# BACKPMAN30_PwrSw.net
KiCad netlist of a schematic drawn in Altium Designer
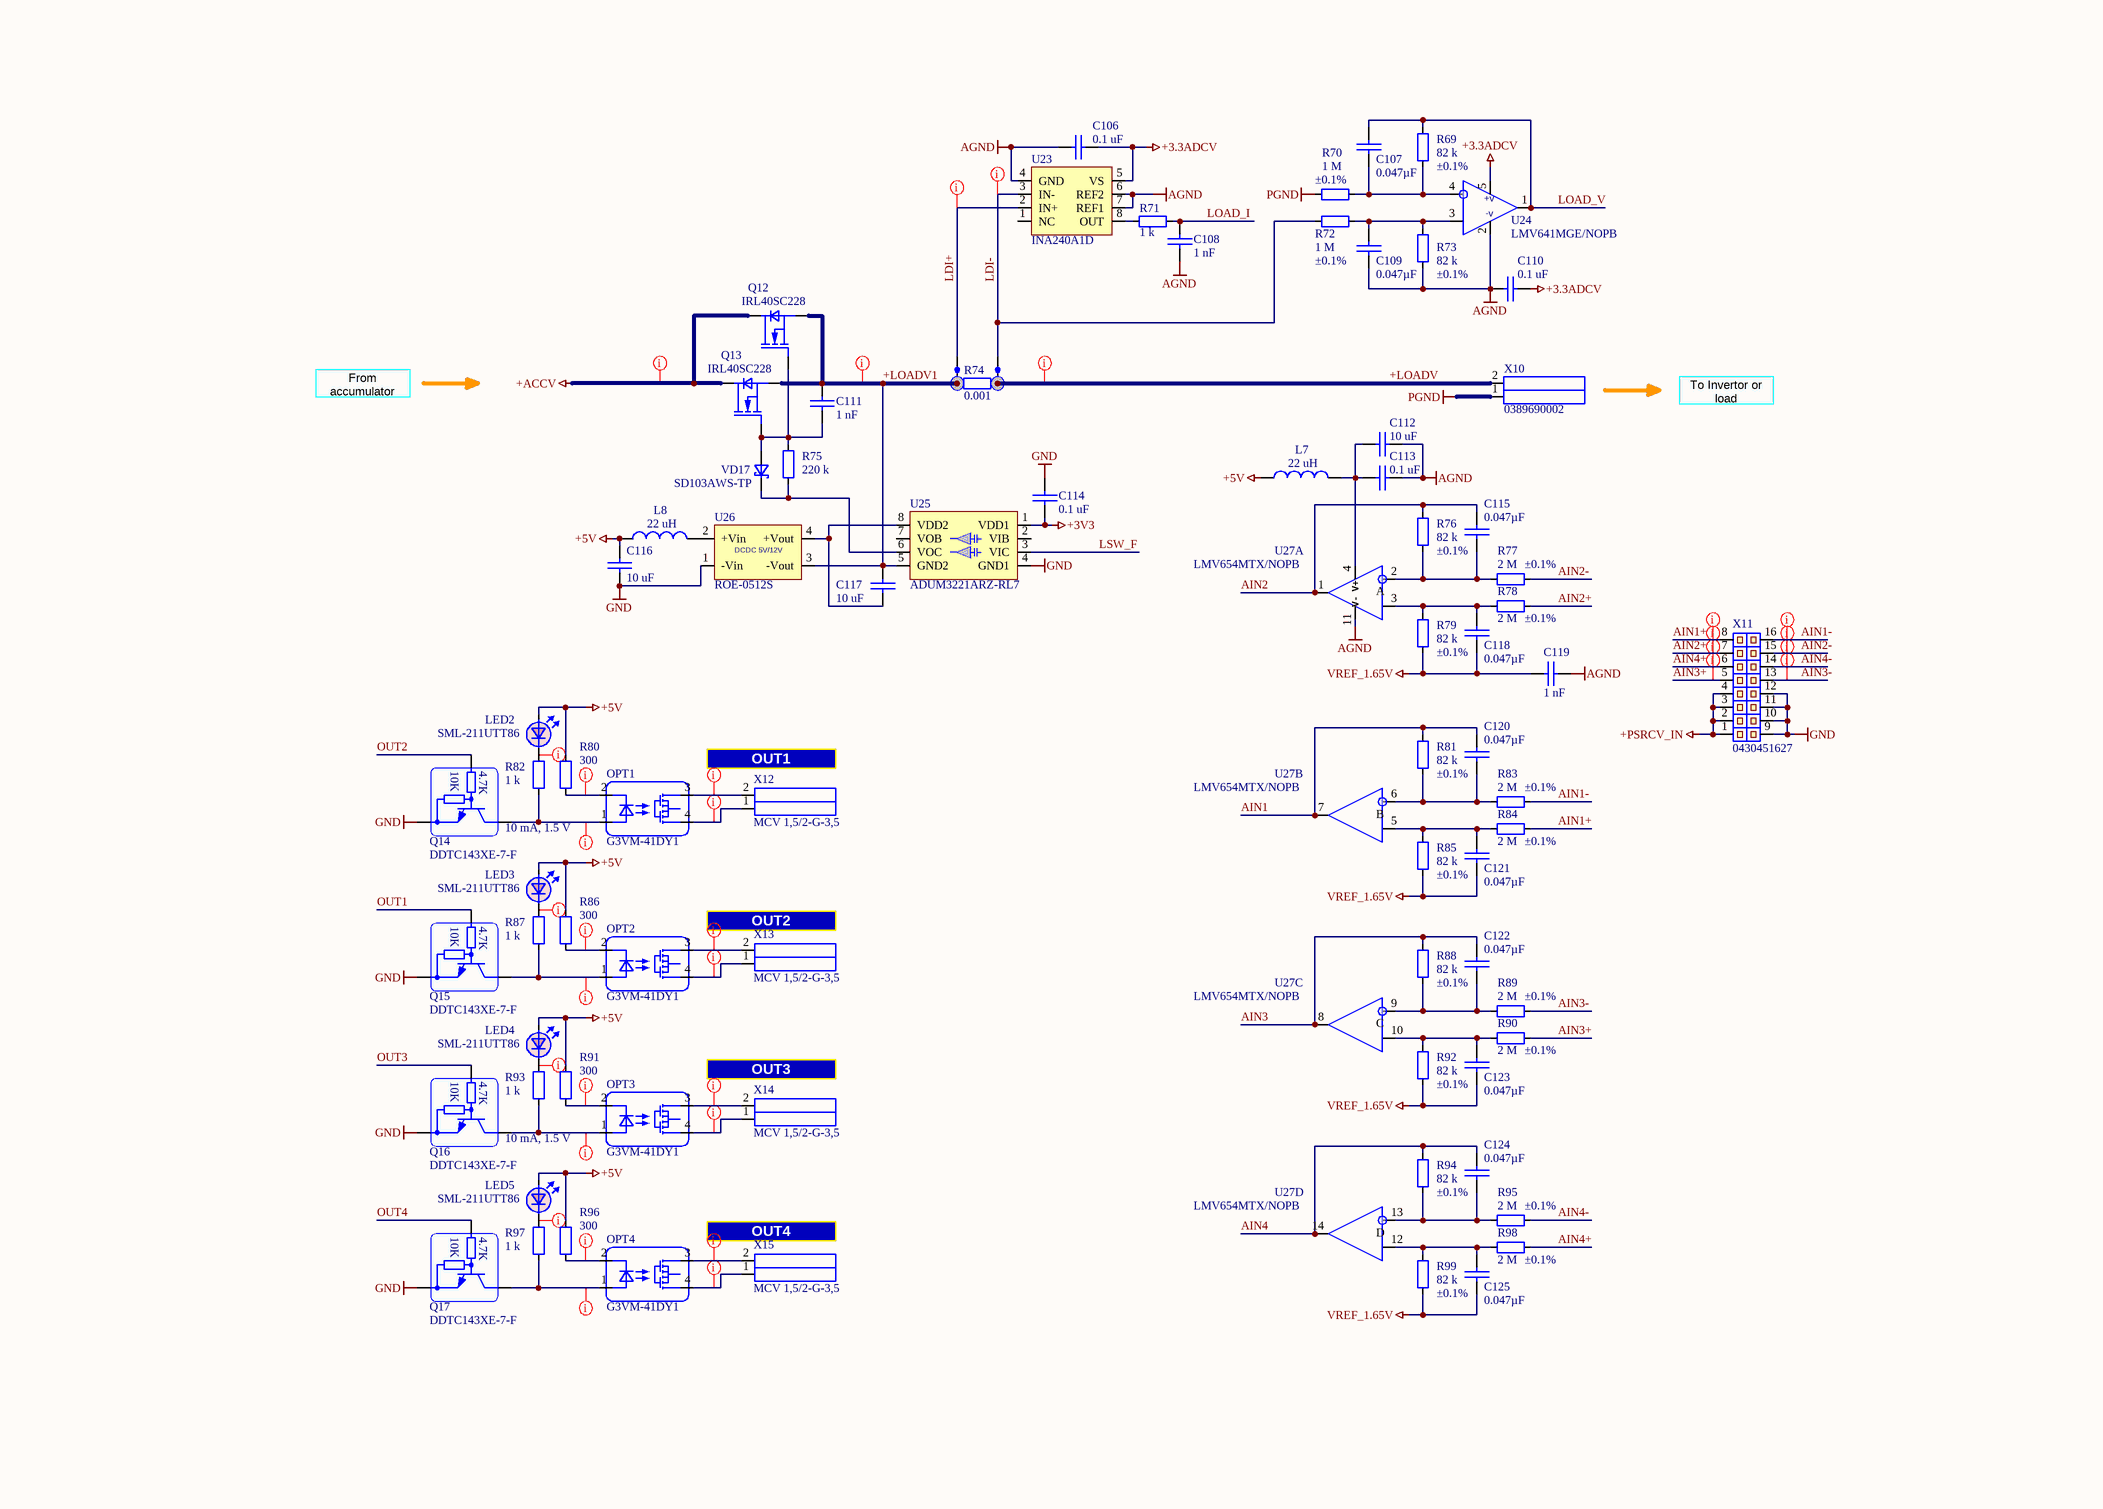
[diagram p0: BACKPMAN30_PwrSw.SchDoc]

(export (version "E")
  (design (tool "Eeschema 10.0.6"))
  (components
    (comp (ref "B4")
      (value "Net tie 0.3mm")
      (footprint "Net tee 0.3 mm")
      (libsource (lib "ea_Mechanical") (part "Net tie 0.3mm"))
    )
    (comp (ref "B5")
      (value "Net tie 0.3mm")
      (footprint "Net tee 0.3 mm")
      (libsource (lib "ea_Mechanical") (part "Net tie 0.3mm"))
    )
    (comp (ref "C106")
      (value "0.1 uF")
      (footprint "1608[0603]")
      (description "0.1 µF ±10% 50V Ceramic Capacitor X7R 0603 (1608 Metric), -55°C ~ 125°C")
      (fields
        (field (name "MANUFACTURER") "Walsin Technology Corporation")
        (field (name "PARTNUM") "1292-1643-1-ND")
      )
      (libsource (lib "ea_Capacitors_0603") (part "0603B104K500CT"))
    )
    (comp (ref "C107")
      (value "0.047µF")
      (footprint "0603 CAP")
      (description "0.047µF, ±5%, 50V, X7R, 0603 (1608 Metric), -55°C ~ 125°C, -, General Purpose")
      (fields (field (name "PART NUMBER") "CC0603JRX7R9BB473") (field (name "MANUFACTURER") "Yageo"))
      (libsource (lib "ea_PassivComps") (part "Capacitor"))
    )
    (comp (ref "C108")
      (value "1 nF")
      (footprint "0603 CAP")
      (description "1000pF, ±5%, 50V, X7R, 0603 (1608 Metric), -55°C ~ 125°C, -, General Purpose")
      (fields (field (name "PART NUMBER") "CC0603JRX7R9BB102") (field (name "MANUFACTURER") "Yageo"))
      (libsource (lib "ea_PassivComps") (part "Capacitor"))
    )
    (comp (ref "C109")
      (value "0.047µF")
      (footprint "0603 CAP")
      (description "0.047µF, ±5%, 50V, X7R, 0603 (1608 Metric), -55°C ~ 125°C, -, General Purpose")
      (fields (field (name "PART NUMBER") "CC0603JRX7R9BB473") (field (name "MANUFACTURER") "Yageo"))
      (libsource (lib "ea_PassivComps") (part "Capacitor"))
    )
    (comp (ref "C110")
      (value "0.1 uF")
      (footprint "1608[0603]")
      (description "0.1 µF ±10% 50V Ceramic Capacitor X7R 0603 (1608 Metric), -55°C ~ 125°C")
      (fields
        (field (name "MANUFACTURER") "Walsin Technology Corporation")
        (field (name "PARTNUM") "1292-1643-1-ND")
      )
      (libsource (lib "ea_Capacitors_0603") (part "0603B104K500CT"))
    )
    (comp (ref "C111")
      (value "1 nF")
      (footprint "0603 CAP")
      (description "1000pF, ±5%, 50V, X7R, 0603 (1608 Metric), -55°C ~ 125°C, -, General Purpose")
      (fields (field (name "PART NUMBER") "CC0603JRX7R9BB102") (field (name "MANUFACTURER") "Yageo"))
      (libsource (lib "ea_PassivComps") (part "Capacitor"))
    )
    (comp (ref "C112")
      (value "10 uF")
      (footprint "3225[1210]")
      (description "10 µF ±10%, 50V, Ceramic Capacitor X7R, 1210 (3225 Metric), -55°C ~ 125°C")
      (fields
        (field (name "MANUFACTURER") "CAL-CHIP ELECTRONICS, INC.")
        (field (name "PARTNUM") "2571-GMC32X7R106K50NTTR-ND")
      )
      (libsource (lib "ea_Capacitors_1210") (part "GMC32X7R106K50NT"))
    )
    (comp (ref "C113")
      (value "0.1 uF")
      (footprint "1608[0603]")
      (description "0.1 µF ±10% 50V Ceramic Capacitor X7R 0603 (1608 Metric), -55°C ~ 125°C")
      (fields
        (field (name "MANUFACTURER") "Walsin Technology Corporation")
        (field (name "PARTNUM") "1292-1643-1-ND")
      )
      (libsource (lib "ea_Capacitors_0603") (part "0603B104K500CT"))
    )
    (comp (ref "C114")
      (value "0.1 uF")
      (footprint "1608[0603]")
      (description "0.1 µF ±10% 50V Ceramic Capacitor X7R 0603 (1608 Metric), -55°C ~ 125°C")
      (fields
        (field (name "TOLERANCE") "+-10%")
        (field (name "MANUFACTURER") "Walsin Technology Corporation")
      )
      (libsource (lib "ea_Capacitors_0603") (part "0603B104K500CT"))
    )
    (comp (ref "C115")
      (value "0.047µF")
      (footprint "0603 CAP")
      (description "0.047µF, ±5%, 50V, X7R, 0603 (1608 Metric), -55°C ~ 125°C, -, General Purpose")
      (fields (field (name "PART NUMBER") "CC0603JRX7R9BB473") (field (name "MANUFACTURER") "Yageo"))
      (libsource (lib "ea_PassivComps") (part "Capacitor"))
    )
    (comp (ref "C116")
      (value "10 uF")
      (footprint "3225[1210]")
      (description "10 µF ±10%, 50V, Ceramic Capacitor X7R, 1210 (3225 Metric), -55°C ~ 125°C")
      (fields
        (field (name "MANUFACTURER") "CAL-CHIP ELECTRONICS, INC.")
        (field (name "PARTNUM") "2571-GMC32X7R106K50NTTR-ND")
      )
      (libsource (lib "ea_Capacitors_1210") (part "GMC32X7R106K50NT"))
    )
    (comp (ref "C117")
      (value "10 uF")
      (footprint "3225[1210]")
      (description "10 µF ±10%, 50V, Ceramic Capacitor X7R, 1210 (3225 Metric), -55°C ~ 125°C")
      (fields
        (field (name "MANUFACTURER") "CAL-CHIP ELECTRONICS, INC.")
        (field (name "PARTNUM") "2571-GMC32X7R106K50NTTR-ND")
      )
      (libsource (lib "ea_Capacitors_1210") (part "GMC32X7R106K50NT"))
    )
    (comp (ref "C118")
      (value "0.047µF")
      (footprint "0603 CAP")
      (description "0.047µF, ±5%, 50V, X7R, 0603 (1608 Metric), -55°C ~ 125°C, -, General Purpose")
      (fields (field (name "PART NUMBER") "CC0603JRX7R9BB473") (field (name "MANUFACTURER") "Yageo"))
      (libsource (lib "ea_PassivComps") (part "Capacitor"))
    )
    (comp (ref "C119")
      (value "1 nF")
      (footprint "0603 CAP")
      (description "1000pF, ±5%, 50V, X7R, 0603 (1608 Metric), -55°C ~ 125°C, -, General Purpose")
      (fields (field (name "PART NUMBER") "CC0603JRX7R9BB102") (field (name "MANUFACTURER") "Yageo"))
      (libsource (lib "ea_PassivComps") (part "Capacitor"))
    )
    (comp (ref "C120")
      (value "0.047µF")
      (footprint "0603 CAP")
      (description "0.047µF, ±5%, 50V, X7R, 0603 (1608 Metric), -55°C ~ 125°C, -, General Purpose")
      (fields (field (name "PART NUMBER") "CC0603JRX7R9BB473") (field (name "MANUFACTURER") "Yageo"))
      (libsource (lib "ea_PassivComps") (part "Capacitor"))
    )
    (comp (ref "C121")
      (value "0.047µF")
      (footprint "0603 CAP")
      (description "0.047µF, ±5%, 50V, X7R, 0603 (1608 Metric), -55°C ~ 125°C, -, General Purpose")
      (fields (field (name "PART NUMBER") "CC0603JRX7R9BB473") (field (name "MANUFACTURER") "Yageo"))
      (libsource (lib "ea_PassivComps") (part "Capacitor"))
    )
    (comp (ref "C122")
      (value "0.047µF")
      (footprint "0603 CAP")
      (description "0.047µF, ±5%, 50V, X7R, 0603 (1608 Metric), -55°C ~ 125°C, -, General Purpose")
      (fields (field (name "PART NUMBER") "CC0603JRX7R9BB473") (field (name "MANUFACTURER") "Yageo"))
      (libsource (lib "ea_PassivComps") (part "Capacitor"))
    )
    (comp (ref "C123")
      (value "0.047µF")
      (footprint "0603 CAP")
      (description "0.047µF, ±5%, 50V, X7R, 0603 (1608 Metric), -55°C ~ 125°C, -, General Purpose")
      (fields (field (name "PART NUMBER") "CC0603JRX7R9BB473") (field (name "MANUFACTURER") "Yageo"))
      (libsource (lib "ea_PassivComps") (part "Capacitor"))
    )
    (comp (ref "C124")
      (value "0.047µF")
      (footprint "0603 CAP")
      (description "0.047µF, ±5%, 50V, X7R, 0603 (1608 Metric), -55°C ~ 125°C, -, General Purpose")
      (fields (field (name "PART NUMBER") "CC0603JRX7R9BB473") (field (name "MANUFACTURER") "Yageo"))
      (libsource (lib "ea_PassivComps") (part "Capacitor"))
    )
    (comp (ref "C125")
      (value "0.047µF")
      (footprint "0603 CAP")
      (description "0.047µF, ±5%, 50V, X7R, 0603 (1608 Metric), -55°C ~ 125°C, -, General Purpose")
      (fields (field (name "PART NUMBER") "CC0603JRX7R9BB473") (field (name "MANUFACTURER") "Yageo"))
      (libsource (lib "ea_PassivComps") (part "Capacitor"))
    )
    (comp (ref "L7")
      (value "22 uH")
      (footprint "2518")
      (description "22 µH Unshielded Wirewound Inductor, 490 mA, 560mOhm, 1007 (2518 Metric)")
      (fields (field (name "MANUFACTURER") "Taiyo Yuden") (field (name "PARTNUM") "587-2439-1-ND"))
      (libsource (lib "ea_Inductors") (part "BRC2518T220K"))
    )
    (comp (ref "L8")
      (value "22 uH")
      (footprint "2518")
      (description "22 µH Unshielded Wirewound Inductor, 490 mA, 560mOhm, 1007 (2518 Metric)")
      (fields (field (name "MANUFACTURER") "Taiyo Yuden") (field (name "PARTNUM") "587-2439-1-ND"))
      (libsource (lib "ea_Inductors") (part "BRC2518T220K"))
    )
    (comp (ref "LED2")
      (value "SML-211UTT86")
      (footprint "0805 LED")
      (description "0805 red LED, hibright, 2 mA, 1.8V, 130°")
      (fields (field (name "MANUFACTURER") "Rohm") (field (name "PARTNUM") "511-1292-1-ND"))
      (libsource (lib "ea_Indicators") (part "SML-211UTT86"))
    )
    (comp (ref "LED3")
      (value "SML-211UTT86")
      (footprint "0805 LED")
      (description "0805 red LED, hibright, 2 mA, 1.8V, 130°")
      (fields (field (name "MANUFACTURER") "Rohm") (field (name "PARTNUM") "511-1292-1-ND"))
      (libsource (lib "ea_Indicators") (part "SML-211UTT86"))
    )
    (comp (ref "LED4")
      (value "SML-211UTT86")
      (footprint "0805 LED")
      (description "0805 red LED, hibright, 2 mA, 1.8V, 130°")
      (fields (field (name "MANUFACTURER") "Rohm") (field (name "PARTNUM") "511-1292-1-ND"))
      (libsource (lib "ea_Indicators") (part "SML-211UTT86"))
    )
    (comp (ref "LED5")
      (value "SML-211UTT86")
      (footprint "0805 LED")
      (description "0805 red LED, hibright, 2 mA, 1.8V, 130°")
      (fields (field (name "MANUFACTURER") "Rohm") (field (name "PARTNUM") "511-1292-1-ND"))
      (libsource (lib "ea_Indicators") (part "SML-211UTT86"))
    )
    (comp (ref "OPT1")
      (value "G3VM-41DY1")
      (footprint "4-SMD Omron")
      (description "Solid State AC DC SPST-NO (1 Form A), 0-40V, 2A, 4-SMD (0.300\", 7.62mm)")
      (fields
        (field (name "MANUFACTURER") "Omron Electronics Inc-EMC Div")
        (field (name "PARTNUM") "Z5418CT-ND")
      )
      (libsource (lib "ea_Opto") (part "G3VM-41DY1"))
    )
    (comp (ref "OPT2")
      (value "G3VM-41DY1")
      (footprint "4-SMD Omron")
      (description "Solid State AC DC SPST-NO (1 Form A), 0-40V, 2A, 4-SMD (0.300\", 7.62mm)")
      (fields
        (field (name "MANUFACTURER") "Omron Electronics Inc-EMC Div")
        (field (name "PARTNUM") "Z5418CT-ND")
      )
      (libsource (lib "ea_Opto") (part "G3VM-41DY1"))
    )
    (comp (ref "OPT3")
      (value "G3VM-41DY1")
      (footprint "4-SMD Omron")
      (description "Solid State AC DC SPST-NO (1 Form A), 0-40V, 2A, 4-SMD (0.300\", 7.62mm)")
      (fields
        (field (name "MANUFACTURER") "Omron Electronics Inc-EMC Div")
        (field (name "PARTNUM") "Z5418CT-ND")
      )
      (libsource (lib "ea_Opto") (part "G3VM-41DY1"))
    )
    (comp (ref "OPT4")
      (value "G3VM-41DY1")
      (footprint "4-SMD Omron")
      (description "Solid State AC DC SPST-NO (1 Form A), 0-40V, 2A, 4-SMD (0.300\", 7.62mm)")
      (fields
        (field (name "MANUFACTURER") "Omron Electronics Inc-EMC Div")
        (field (name "PARTNUM") "Z5418CT-ND")
      )
      (libsource (lib "ea_Opto") (part "G3VM-41DY1"))
    )
    (comp (ref "Q12")
      (value "IRL40SC228")
      (footprint "D2Pak-7pin")
      (description "N-Channel 40 V 557A (Tc) 416W (Tc), 0.65mOhm @ 100A, 10V,  Surface Mount D2PAK (7-Lead)")
      (fields
        (field (name "MANUFACTURER") "Infineon Technologies")
        (field (name "PARTNUM") "IRL40SC228CT-ND")
      )
      (libsource (lib "ea_MOSFET_&_drivers") (part "IRL40SC228"))
    )
    (comp (ref "Q13")
      (value "IRL40SC228")
      (footprint "D2Pak-7pin")
      (description "N-Channel 40 V 557A (Tc) 416W (Tc), 0.65mOhm @ 100A, 10V,  Surface Mount D2PAK (7-Lead)")
      (fields
        (field (name "MANUFACTURER") "Infineon Technologies")
        (field (name "PARTNUM") "IRL40SC228CT-ND")
      )
      (libsource (lib "ea_MOSFET_&_drivers") (part "IRL40SC228"))
    )
    (comp (ref "Q14")
      (value "DDTC143XE-7-F")
      (footprint "SOT-523F")
      (fields
        (field (name "MANUFACTURER") "Diodes Incorporated")
        (field (name "PARTNUM") "DDTC143XE-FDICT-ND")
      )
      (libsource (lib "ea_Transistors") (part "DDTC143XE-7-F"))
    )
    (comp (ref "Q15")
      (value "DDTC143XE-7-F")
      (footprint "SOT-523F")
      (fields
        (field (name "MANUFACTURER") "Diodes Incorporated")
        (field (name "PARTNUM") "DDTC143XE-FDICT-ND")
      )
      (libsource (lib "ea_Transistors") (part "DDTC143XE-7-F"))
    )
    (comp (ref "Q16")
      (value "DDTC143XE-7-F")
      (footprint "SOT-523F")
      (fields
        (field (name "MANUFACTURER") "Diodes Incorporated")
        (field (name "PARTNUM") "DDTC143XE-FDICT-ND")
      )
      (libsource (lib "ea_Transistors") (part "DDTC143XE-7-F"))
    )
    (comp (ref "Q17")
      (value "DDTC143XE-7-F")
      (footprint "SOT-523F")
      (fields
        (field (name "MANUFACTURER") "Diodes Incorporated")
        (field (name "PARTNUM") "DDTC143XE-FDICT-ND")
      )
      (libsource (lib "ea_Transistors") (part "DDTC143XE-7-F"))
    )
    (comp (ref "R69")
      (value "82 k")
      (footprint "0603")
      (fields
        (field (name "MANUFACTURER") "Panasonic Electronic Components")
        (field (name "TOLERANCE") "±0.1%")
        (field (name "VOLTAGE") "75V")
        (field (name "PARTNUM") "P82KDBCT-ND")
      )
      (libsource (lib "") (part "Resistor_1"))
    )
    (comp (ref "R70")
      (value "1 M")
      (footprint "0805")
      (description "1M, ±0.1%, ±50ppm/°C, 0.125W, 1/8W Chip Resistor 0805 (2012 Metric) - Thin Film,-55°C ~ 155°C")
      (fields
        (field (name "MANUFACTURER") "YAGEO")
        (field (name "TOLERANCE") "±0.1%")
        (field (name "PARTNUM") "YAG4967CT-ND")
      )
      (libsource (lib "ea_Resistors_0805") (part "RT0805BRE071ML"))
    )
    (comp (ref "R71")
      (value "1 k")
      (footprint "0603")
      (fields
        (field (name "MANUFACTURER") "Stackpole Electronics Inc.")
        (field (name "TOLERANCE") "±1%")
        (field (name "VOLTAGE") "75V")
      )
      (libsource (lib "ea_PassivComps") (part "Resistor"))
    )
    (comp (ref "R72")
      (value "1 M")
      (footprint "0805")
      (description "1M, ±0.1%, ±50ppm/°C, 0.125W, 1/8W Chip Resistor 0805 (2012 Metric) - Thin Film,-55°C ~ 155°C")
      (fields
        (field (name "MANUFACTURER") "YAGEO")
        (field (name "TOLERANCE") "±0.1%")
        (field (name "PARTNUM") "YAG4967CT-ND")
      )
      (libsource (lib "ea_Resistors_0805") (part "RT0805BRE071ML"))
    )
    (comp (ref "R73")
      (value "82 k")
      (footprint "0603")
      (fields
        (field (name "MANUFACTURER") "Panasonic Electronic Components")
        (field (name "TOLERANCE") "±0.1%")
        (field (name "VOLTAGE") "75V")
        (field (name "PARTNUM") "P82KDBCT-ND")
      )
      (libsource (lib "") (part "Resistor_1"))
    )
    (comp (ref "R74")
      (value "0.001")
      (footprint "WSR52L000FEA")
      (description "Curr.sens.res. 0.001 OHM 5W 1% 4527 SMD")
      (fields (field (name "MANUFACTURER") "Vishay/Dale") (field (name "TOLERANCE") "1%"))
      (libsource (lib "ea_Resistors") (part "WSR51L000FEA"))
    )
    (comp (ref "R75")
      (value "220 k")
      (footprint "0603")
      (fields
        (field (name "MANUFACTURER") "Stackpole Electronics Inc.")
        (field (name "TOLERANCE") "±1%")
        (field (name "VOLTAGE") "75V")
      )
      (libsource (lib "") (part "Resistor_1"))
    )
    (comp (ref "R76")
      (value "82 k")
      (footprint "0603")
      (fields
        (field (name "MANUFACTURER") "Panasonic Electronic Components")
        (field (name "TOLERANCE") "±0.1%")
        (field (name "VOLTAGE") "75V")
        (field (name "PARTNUM") "P82KDBCT-ND")
      )
      (libsource (lib "ea_PassivComps") (part "Resistor"))
    )
    (comp (ref "R77")
      (value "2 M")
      (footprint "0805")
      (description "2M, ±0.1%, ±25ppm/°C, 0.125W, 1/8W Chip Resistor 0805 (2012 Metric) - Thin Film,-55°C ~ 155°C")
      (fields
        (field (name "MANUFACTURER") "TE Connectivity Passive Product")
        (field (name "TOLERANCE") "±0.1%")
        (field (name "PARTNUM") "A119974CT-ND")
      )
      (libsource (lib "ea_Resistors_0805") (part "CPF0805B2M0E"))
    )
    (comp (ref "R78")
      (value "2 M")
      (footprint "0805")
      (description "2M, ±0.1%, ±25ppm/°C, 0.125W, 1/8W Chip Resistor 0805 (2012 Metric) - Thin Film,-55°C ~ 155°C")
      (fields
        (field (name "MANUFACTURER") "TE Connectivity Passive Product")
        (field (name "TOLERANCE") "±0.1%")
        (field (name "PARTNUM") "A119974CT-ND")
      )
      (libsource (lib "ea_Resistors_0805") (part "CPF0805B2M0E"))
    )
    (comp (ref "R79")
      (value "82 k")
      (footprint "0603")
      (fields
        (field (name "MANUFACTURER") "Panasonic Electronic Components")
        (field (name "TOLERANCE") "±0.1%")
        (field (name "VOLTAGE") "75V")
        (field (name "PARTNUM") "P82KDBCT-ND")
      )
      (libsource (lib "ea_PassivComps") (part "Resistor"))
    )
    (comp (ref "R80")
      (value "300")
      (footprint "0603")
      (fields
        (field (name "MANUFACTURER") "Stackpole Electronics Inc.")
        (field (name "TOLERANCE") "±1%")
        (field (name "VOLTAGE") "75V")
      )
      (libsource (lib "") (part "Resistor_1"))
    )
    (comp (ref "R81")
      (value "82 k")
      (footprint "0603")
      (fields
        (field (name "MANUFACTURER") "Panasonic Electronic Components")
        (field (name "TOLERANCE") "±0.1%")
        (field (name "VOLTAGE") "75V")
        (field (name "PARTNUM") "P82KDBCT-ND")
      )
      (libsource (lib "ea_PassivComps") (part "Resistor"))
    )
    (comp (ref "R82")
      (value "1 k")
      (footprint "0603")
      (fields
        (field (name "MANUFACTURER") "Stackpole Electronics Inc.")
        (field (name "TOLERANCE") "±1%")
        (field (name "VOLTAGE") "75V")
      )
      (libsource (lib "") (part "Resistor_1"))
    )
    (comp (ref "R83")
      (value "2 M")
      (footprint "0805")
      (description "2M, ±0.1%, ±25ppm/°C, 0.125W, 1/8W Chip Resistor 0805 (2012 Metric) - Thin Film,-55°C ~ 155°C")
      (fields
        (field (name "MANUFACTURER") "TE Connectivity Passive Product")
        (field (name "TOLERANCE") "±0.1%")
        (field (name "PARTNUM") "A119974CT-ND")
      )
      (libsource (lib "ea_Resistors_0805") (part "CPF0805B2M0E"))
    )
    (comp (ref "R84")
      (value "2 M")
      (footprint "0805")
      (description "2M, ±0.1%, ±25ppm/°C, 0.125W, 1/8W Chip Resistor 0805 (2012 Metric) - Thin Film,-55°C ~ 155°C")
      (fields
        (field (name "MANUFACTURER") "TE Connectivity Passive Product")
        (field (name "TOLERANCE") "±0.1%")
        (field (name "PARTNUM") "A119974CT-ND")
      )
      (libsource (lib "ea_Resistors_0805") (part "CPF0805B2M0E"))
    )
    (comp (ref "R85")
      (value "82 k")
      (footprint "0603")
      (fields
        (field (name "MANUFACTURER") "Panasonic Electronic Components")
        (field (name "TOLERANCE") "±0.1%")
        (field (name "VOLTAGE") "75V")
        (field (name "PARTNUM") "P82KDBCT-ND")
      )
      (libsource (lib "ea_PassivComps") (part "Resistor"))
    )
    (comp (ref "R86")
      (value "300")
      (footprint "0603")
      (fields
        (field (name "MANUFACTURER") "Stackpole Electronics Inc.")
        (field (name "TOLERANCE") "±1%")
        (field (name "VOLTAGE") "75V")
      )
      (libsource (lib "") (part "Resistor_1"))
    )
    (comp (ref "R87")
      (value "1 k")
      (footprint "0603")
      (fields
        (field (name "MANUFACTURER") "Stackpole Electronics Inc.")
        (field (name "TOLERANCE") "±1%")
        (field (name "VOLTAGE") "75V")
      )
      (libsource (lib "") (part "Resistor_1"))
    )
    (comp (ref "R88")
      (value "82 k")
      (footprint "0603")
      (fields
        (field (name "MANUFACTURER") "Panasonic Electronic Components")
        (field (name "TOLERANCE") "±0.1%")
        (field (name "VOLTAGE") "75V")
        (field (name "PARTNUM") "P82KDBCT-ND")
      )
      (libsource (lib "ea_PassivComps") (part "Resistor"))
    )
    (comp (ref "R89")
      (value "2 M")
      (footprint "0805")
      (description "2M, ±0.1%, ±25ppm/°C, 0.125W, 1/8W Chip Resistor 0805 (2012 Metric) - Thin Film,-55°C ~ 155°C")
      (fields
        (field (name "MANUFACTURER") "TE Connectivity Passive Product")
        (field (name "TOLERANCE") "±0.1%")
        (field (name "PARTNUM") "A119974CT-ND")
      )
      (libsource (lib "ea_Resistors_0805") (part "CPF0805B2M0E"))
    )
    (comp (ref "R90")
      (value "2 M")
      (footprint "0805")
      (description "2M, ±0.1%, ±25ppm/°C, 0.125W, 1/8W Chip Resistor 0805 (2012 Metric) - Thin Film,-55°C ~ 155°C")
      (fields
        (field (name "MANUFACTURER") "TE Connectivity Passive Product")
        (field (name "TOLERANCE") "±0.1%")
        (field (name "PARTNUM") "A119974CT-ND")
      )
      (libsource (lib "ea_Resistors_0805") (part "CPF0805B2M0E"))
    )
    (comp (ref "R91")
      (value "300")
      (footprint "0603")
      (fields
        (field (name "MANUFACTURER") "Stackpole Electronics Inc.")
        (field (name "TOLERANCE") "±1%")
        (field (name "VOLTAGE") "75V")
      )
      (libsource (lib "") (part "Resistor_1"))
    )
    (comp (ref "R92")
      (value "82 k")
      (footprint "0603")
      (fields
        (field (name "MANUFACTURER") "Panasonic Electronic Components")
        (field (name "TOLERANCE") "±0.1%")
        (field (name "VOLTAGE") "75V")
        (field (name "PARTNUM") "P82KDBCT-ND")
      )
      (libsource (lib "ea_PassivComps") (part "Resistor"))
    )
    (comp (ref "R93")
      (value "1 k")
      (footprint "0603")
      (fields
        (field (name "MANUFACTURER") "Stackpole Electronics Inc.")
        (field (name "TOLERANCE") "±1%")
        (field (name "VOLTAGE") "75V")
      )
      (libsource (lib "") (part "Resistor_1"))
    )
    (comp (ref "R94")
      (value "82 k")
      (footprint "0603")
      (fields
        (field (name "MANUFACTURER") "Panasonic Electronic Components")
        (field (name "TOLERANCE") "±0.1%")
        (field (name "VOLTAGE") "75V")
        (field (name "PARTNUM") "P82KDBCT-ND")
      )
      (libsource (lib "ea_PassivComps") (part "Resistor"))
    )
    (comp (ref "R95")
      (value "2 M")
      (footprint "0805")
      (description "2M, ±0.1%, ±25ppm/°C, 0.125W, 1/8W Chip Resistor 0805 (2012 Metric) - Thin Film,-55°C ~ 155°C")
      (fields
        (field (name "MANUFACTURER") "TE Connectivity Passive Product")
        (field (name "TOLERANCE") "±0.1%")
        (field (name "PARTNUM") "A119974CT-ND")
      )
      (libsource (lib "ea_Resistors_0805") (part "CPF0805B2M0E"))
    )
    (comp (ref "R96")
      (value "300")
      (footprint "0603")
      (fields
        (field (name "MANUFACTURER") "Stackpole Electronics Inc.")
        (field (name "TOLERANCE") "±1%")
        (field (name "VOLTAGE") "75V")
      )
      (libsource (lib "") (part "Resistor_1"))
    )
    (comp (ref "R97")
      (value "1 k")
      (footprint "0603")
      (fields
        (field (name "MANUFACTURER") "Stackpole Electronics Inc.")
        (field (name "TOLERANCE") "±1%")
        (field (name "VOLTAGE") "75V")
      )
      (libsource (lib "") (part "Resistor_1"))
    )
    (comp (ref "R98")
      (value "2 M")
      (footprint "0805")
      (description "2M, ±0.1%, ±25ppm/°C, 0.125W, 1/8W Chip Resistor 0805 (2012 Metric) - Thin Film,-55°C ~ 155°C")
      (fields
        (field (name "MANUFACTURER") "TE Connectivity Passive Product")
        (field (name "TOLERANCE") "±0.1%")
        (field (name "PARTNUM") "A119974CT-ND")
      )
      (libsource (lib "ea_Resistors_0805") (part "CPF0805B2M0E"))
    )
    (comp (ref "R99")
      (value "82 k")
      (footprint "0603")
      (fields
        (field (name "MANUFACTURER") "Panasonic Electronic Components")
        (field (name "TOLERANCE") "±0.1%")
        (field (name "VOLTAGE") "75V")
        (field (name "PARTNUM") "P82KDBCT-ND")
      )
      (libsource (lib "ea_PassivComps") (part "Resistor"))
    )
    (comp (ref "U23")
      (value "INA240A1D")
      (footprint "8-SOIC Linear")
      (description "Current Sense Amplifier, 20V/V, 2V/us, 400KHz, -40°C ~ 125°C, 8-SOIC")
      (fields (field (name "MANUFACTURER") "Texas Instruments") (field (name "PARTNUM") "296-48837-ND"))
      (libsource (lib "ea_IC_OPAmps_AnComparators") (part "INA240A1D"))
    )
    (comp (ref "U24")
      (value "LMV641MGE/NOPB")
      (footprint "SOT-353 ON Semi")
      (description "OpAmp,  Rail-to-Rail,  10MHz, VSS 2.7V ~ 12V, Vofs 30µV,  SC-70-5, -40°C ~ 125°C")
      (fields
        (field (name "MANUFACTURER") "Texas Instruments")
        (field (name "PARTNUM") "LMV641MGE/NOPBCT-ND")
      )
      (libsource (lib "ea_IC_OPAmps_AnComparators") (part "LMV641MGE/NOPB"))
    )
    (comp (ref "U25")
      (value "ADUM3221ARZ-RL7")
      (footprint "8-SOIC Linear")
      (description "4A Gate Driver Magnetic Coupling 2500Vrms 2 Channel 8-SOIC, -40°C ~ 125°C")
      (fields
        (field (name "MANUFACTURER") "Analog Devices Inc.")
        (field (name "PARTNUM") "ADUM3221ARZ-RL7CT-ND")
      )
      (libsource (lib "ea_IC_Isolated_Interfaces") (part "ADUM3221ARZ-RL7"))
    )
    (comp (ref "U26")
      (value "ROE-0512S")
      (footprint "Recom 4-SIP module")
      (description "Isolated Module DC DC Converter 1 Output 12V - - 84mA 4.5V - 5.5V Input")
      (fields (field (name "MANUFACTURER") "Recom Power") (field (name "PARTNUM") "ROE-0512S-ND"))
      (libsource (lib "ea_PowerSources") (part "ROE-0512S"))
    )
    (comp (ref "U27")
      (value "LMV654MTX/NOPB")
      (footprint "14 TSSOP Maxim")
      (fields (field (name "MANUFACTURER") "Texas Instruments") (field (name "PARTNUM") "296-42685-1-ND"))
      (libsource (lib "ea_IC_OPAmps_AnComparators") (part "LMV654MTX/NOPB"))
    )
    (comp (ref "VD17")
      (value "SD103AWS-TP")
      (footprint "SOD323")
      (description "Diode Schottky 40 V 350mA Surface Mount SOD-323, -65°C ~ 125°C")
      (fields
        (field (name "PARTNAME") "SD103AWS-TP")
        (field (name "MANUFACTURER") "Micro Commercial Co")
        (field (name "PARTNUM") "SD103AWSTPMSCT-ND")
      )
      (libsource (lib "ea_Diodes") (part "SD103AWS-TP"))
    )
    (comp (ref "X10")
      (value "0389690002")
      (footprint "Molex 389690002")
      (description "2 Circuit 0.500\" (12.70mm) Barrier Block Connector Screws with Captive Plate, 50A, 600V, 8-20AWG")
      (fields (field (name "MANUFACTURER") "Molex") (field (name "PARTNUM") "WM7469-ND"))
      (libsource (lib "ea_Connectors_Power") (part "0389690002"))
    )
    (comp (ref "X11")
      (value "0430451627")
      (footprint "0430451627")
      (description "Connector Header Through Hole 16 position 0.118\" (3.00mm)")
      (fields (field (name "MANUFACTURER") "Molex") (field (name "PARTNUM") "WM10708-ND"))
      (libsource (lib "ea_Connectors_3.0_mm_pitch") (part "0430451627"))
    )
    (comp (ref "X12")
      (value "MCV 1,5/2-G-3,5")
      (footprint "mcv1.5-2-g_3.5 Green  + MC 1,5 2-ST-3,5 - 1840366")
      (description "HEADER, VERTICAL, 3.5MM, 2WAY")
      (fields (field (name "MANUFACTURER") "PHOENIX CONTACT") (field (name "PARTNUM") "1843606"))
      (libsource (lib "ea_PhoenixContacts") (part "MCV 1,5/2-G-3,5"))
    )
    (comp (ref "X13")
      (value "MCV 1,5/2-G-3,5")
      (footprint "mcv1.5-2-g_3.5 Green  + MC 1,5 2-ST-3,5 - 1840366")
      (description "HEADER, VERTICAL, 3.5MM, 2WAY")
      (fields (field (name "MANUFACTURER") "PHOENIX CONTACT") (field (name "PARTNUM") "1843606"))
      (libsource (lib "ea_PhoenixContacts") (part "MCV 1,5/2-G-3,5"))
    )
    (comp (ref "X14")
      (value "MCV 1,5/2-G-3,5")
      (footprint "mcv1.5-2-g_3.5 Green  + MC 1,5 2-ST-3,5 - 1840366")
      (description "HEADER, VERTICAL, 3.5MM, 2WAY")
      (fields (field (name "MANUFACTURER") "PHOENIX CONTACT") (field (name "PARTNUM") "1843606"))
      (libsource (lib "ea_PhoenixContacts") (part "MCV 1,5/2-G-3,5"))
    )
    (comp (ref "X15")
      (value "MCV 1,5/2-G-3,5")
      (footprint "mcv1.5-2-g_3.5 Green  + MC 1,5 2-ST-3,5 - 1840366")
      (description "HEADER, VERTICAL, 3.5MM, 2WAY")
      (fields (field (name "MANUFACTURER") "PHOENIX CONTACT") (field (name "PARTNUM") "1843606"))
      (libsource (lib "ea_PhoenixContacts") (part "MCV 1,5/2-G-3,5"))
    )
  )
  (nets
    (net (code "1") (name "+3.3ADCV") (class "Default")
      (node (ref "C106") (pin "1") (pinfunction "1_1") (pintype "passive"))
      (node (ref "C110") (pin "1") (pinfunction "1_1") (pintype "passive"))
      (node (ref "U23") (pin "5") (pinfunction "VS_5") (pintype "passive"))
      (node (ref "U24") (pin "5") (pinfunction "V+_5") (pintype "power_in"))
    )
    (net (code "2") (name "+3V3") (class "Default")
      (node (ref "C114") (pin "1") (pinfunction "1_1") (pintype "passive"))
      (node (ref "U25") (pin "1") (pinfunction "VDD1_1") (pintype "passive"))
    )
    (net (code "3") (name "+5V") (class "Default")
      (node (ref "C116") (pin "1") (pinfunction "1_1") (pintype "passive"))
      (node (ref "L7") (pin "1") (pinfunction "1_1") (pintype "passive"))
      (node (ref "L8") (pin "1") (pinfunction "1_1") (pintype "passive"))
      (node (ref "LED2") (pin "1") (pinfunction "1_1") (pintype "passive"))
      (node (ref "LED3") (pin "1") (pinfunction "1_1") (pintype "passive"))
      (node (ref "LED4") (pin "1") (pinfunction "1_1") (pintype "passive"))
      (node (ref "LED5") (pin "1") (pinfunction "1_1") (pintype "passive"))
      (node (ref "R80") (pin "2") (pinfunction "2_2") (pintype "passive"))
      (node (ref "R86") (pin "2") (pinfunction "2_2") (pintype "passive"))
      (node (ref "R91") (pin "2") (pinfunction "2_2") (pintype "passive"))
      (node (ref "R96") (pin "2") (pinfunction "2_2") (pintype "passive"))
    )
    (net (code "4") (name "+ACCV") (class "Default")
      (node (ref "Q12") (pin "2") (pinfunction "D_2") (pintype "passive"))
      (node (ref "Q13") (pin "2") (pinfunction "D_2") (pintype "passive"))
    )
    (net (code "5") (name "+PSRCV_IN") (class "Default")
      (node (ref "X11") (pin "1") (pinfunction "1_1") (pintype "passive"))
      (node (ref "X11") (pin "2") (pinfunction "2_2") (pintype "passive"))
      (node (ref "X11") (pin "3") (pinfunction "3_3") (pintype "passive"))
      (node (ref "X11") (pin "4") (pinfunction "4_4") (pintype "passive"))
    )
    (net (code "6") (name "/+LOADV") (class "Default")
      (node (ref "B5") (pin "1") (pinfunction "1_1") (pintype "passive"))
      (node (ref "R74") (pin "1") (pinfunction "1_1") (pintype "passive"))
      (node (ref "X10") (pin "2") (pinfunction "2_2") (pintype "passive"))
    )
    (net (code "7") (name "/+LOADV1") (class "Default")
      (node (ref "B4") (pin "1") (pinfunction "1_1") (pintype "passive"))
      (node (ref "C111") (pin "2") (pinfunction "2_2") (pintype "passive"))
      (node (ref "C117") (pin "1") (pinfunction "1_1") (pintype "passive"))
      (node (ref "Q12") (pin "3") (pinfunction "S_3") (pintype "passive"))
      (node (ref "Q13") (pin "3") (pinfunction "S_3") (pintype "passive"))
      (node (ref "R74") (pin "2") (pinfunction "2_2") (pintype "passive"))
      (node (ref "U25") (pin "5") (pinfunction "GND2_5") (pintype "passive"))
      (node (ref "U26") (pin "3") (pinfunction "-Vout_3") (pintype "passive"))
    )
    (net (code "8") (name "/AIN1") (class "Default")
      (node (ref "C120") (pin "1") (pinfunction "1_1") (pintype "passive"))
      (node (ref "R81") (pin "2") (pinfunction "2_2") (pintype "passive"))
      (node (ref "U27") (pin "7") (pinfunction "OUT_7") (pintype "passive"))
    )
    (net (code "9") (name "/AIN1+") (class "Default")
      (node (ref "R84") (pin "1") (pinfunction "1_1") (pintype "passive"))
      (node (ref "X11") (pin "8") (pinfunction "8_8") (pintype "passive"))
    )
    (net (code "10") (name "/AIN1-") (class "Default")
      (node (ref "R83") (pin "1") (pinfunction "1_1") (pintype "passive"))
      (node (ref "X11") (pin "16") (pinfunction "16_16") (pintype "passive"))
    )
    (net (code "11") (name "/AIN2") (class "Default")
      (node (ref "C115") (pin "1") (pinfunction "1_1") (pintype "passive"))
      (node (ref "R76") (pin "2") (pinfunction "2_2") (pintype "passive"))
      (node (ref "U27") (pin "1") (pinfunction "OUT_1") (pintype "passive"))
    )
    (net (code "12") (name "/AIN2+") (class "Default")
      (node (ref "R78") (pin "1") (pinfunction "1_1") (pintype "passive"))
      (node (ref "X11") (pin "7") (pinfunction "7_7") (pintype "passive"))
    )
    (net (code "13") (name "/AIN2-") (class "Default")
      (node (ref "R77") (pin "1") (pinfunction "1_1") (pintype "passive"))
      (node (ref "X11") (pin "15") (pinfunction "15_15") (pintype "passive"))
    )
    (net (code "14") (name "/AIN3") (class "Default")
      (node (ref "C122") (pin "1") (pinfunction "1_1") (pintype "passive"))
      (node (ref "R88") (pin "2") (pinfunction "2_2") (pintype "passive"))
      (node (ref "U27") (pin "8") (pinfunction "OUT_8") (pintype "passive"))
    )
    (net (code "15") (name "/AIN3+") (class "Default")
      (node (ref "R90") (pin "1") (pinfunction "1_1") (pintype "passive"))
      (node (ref "X11") (pin "5") (pinfunction "5_5") (pintype "passive"))
    )
    (net (code "16") (name "/AIN3-") (class "Default")
      (node (ref "R89") (pin "1") (pinfunction "1_1") (pintype "passive"))
      (node (ref "X11") (pin "13") (pinfunction "13_13") (pintype "passive"))
    )
    (net (code "17") (name "/AIN4") (class "Default")
      (node (ref "C124") (pin "1") (pinfunction "1_1") (pintype "passive"))
      (node (ref "R94") (pin "2") (pinfunction "2_2") (pintype "passive"))
      (node (ref "U27") (pin "14") (pinfunction "OUT_14") (pintype "passive"))
    )
    (net (code "18") (name "/AIN4+") (class "Default")
      (node (ref "R98") (pin "1") (pinfunction "1_1") (pintype "passive"))
      (node (ref "X11") (pin "6") (pinfunction "6_6") (pintype "passive"))
    )
    (net (code "19") (name "/AIN4-") (class "Default")
      (node (ref "R95") (pin "1") (pinfunction "1_1") (pintype "passive"))
      (node (ref "X11") (pin "14") (pinfunction "14_14") (pintype "passive"))
    )
    (net (code "20") (name "/LDI+") (class "Default")
      (node (ref "B4") (pin "2") (pinfunction "2_2") (pintype "passive"))
      (node (ref "U23") (pin "2") (pinfunction "IN+_2") (pintype "passive"))
    )
    (net (code "21") (name "/LDI-") (class "Default")
      (node (ref "B5") (pin "2") (pinfunction "2_2") (pintype "passive"))
      (node (ref "R72") (pin "1") (pinfunction "1_1") (pintype "passive"))
      (node (ref "U23") (pin "3") (pinfunction "IN-_3") (pintype "passive"))
    )
    (net (code "22") (name "/LOAD_I") (class "Default")
      (node (ref "C108") (pin "2") (pinfunction "2_2") (pintype "passive"))
      (node (ref "R71") (pin "2") (pinfunction "2_2") (pintype "passive"))
    )
    (net (code "23") (name "/LOAD_V") (class "Default")
      (node (ref "C107") (pin "1") (pinfunction "1_1") (pintype "passive"))
      (node (ref "R69") (pin "2") (pinfunction "2_2") (pintype "passive"))
      (node (ref "U24") (pin "1") (pinfunction "OUT_1") (pintype "passive"))
    )
    (net (code "24") (name "/LSW_F") (class "Default")
      (node (ref "U25") (pin "3") (pinfunction "VIC_3") (pintype "passive"))
    )
    (net (code "25") (name "/OUT1") (class "Default")
      (node (ref "Q15") (pin "1") (pinfunction "B_1") (pintype "passive"))
    )
    (net (code "26") (name "/OUT2") (class "Default")
      (node (ref "Q14") (pin "1") (pinfunction "B_1") (pintype "passive"))
    )
    (net (code "27") (name "/OUT3") (class "Default")
      (node (ref "Q16") (pin "1") (pinfunction "B_1") (pintype "passive"))
    )
    (net (code "28") (name "/OUT4") (class "Default")
      (node (ref "Q17") (pin "1") (pinfunction "B_1") (pintype "passive"))
    )
    (net (code "29") (name "AGND") (class "Default")
      (node (ref "C106") (pin "2") (pinfunction "2_2") (pintype "passive"))
      (node (ref "C108") (pin "1") (pinfunction "1_1") (pintype "passive"))
      (node (ref "C109") (pin "2") (pinfunction "2_2") (pintype "passive"))
      (node (ref "C110") (pin "2") (pinfunction "2_2") (pintype "passive"))
      (node (ref "C112") (pin "2") (pinfunction "2_2") (pintype "passive"))
      (node (ref "C113") (pin "2") (pinfunction "2_2") (pintype "passive"))
      (node (ref "C119") (pin "1") (pinfunction "1_1") (pintype "passive"))
      (node (ref "R73") (pin "1") (pinfunction "1_1") (pintype "passive"))
      (node (ref "U23") (pin "4") (pinfunction "GND_4") (pintype "passive"))
      (node (ref "U23") (pin "6") (pinfunction "REF2_6") (pintype "passive"))
      (node (ref "U23") (pin "7") (pinfunction "REF1_7") (pintype "passive"))
      (node (ref "U24") (pin "2") (pinfunction "GND_2") (pintype "power_in"))
      (node (ref "U27") (pin "11") (pinfunction "V-_11") (pintype "power_in"))
    )
    (net (code "30") (name "GND") (class "Default")
      (node (ref "C114") (pin "2") (pinfunction "2_2") (pintype "passive"))
      (node (ref "C116") (pin "2") (pinfunction "2_2") (pintype "passive"))
      (node (ref "Q14") (pin "2") (pinfunction "E_2") (pintype "passive"))
      (node (ref "Q15") (pin "2") (pinfunction "E_2") (pintype "passive"))
      (node (ref "Q16") (pin "2") (pinfunction "E_2") (pintype "passive"))
      (node (ref "Q17") (pin "2") (pinfunction "E_2") (pintype "passive"))
      (node (ref "U25") (pin "4") (pinfunction "GND1_4") (pintype "passive"))
      (node (ref "U26") (pin "1") (pinfunction "-Vin_1") (pintype "passive"))
      (node (ref "X11") (pin "10") (pinfunction "10_10") (pintype "passive"))
      (node (ref "X11") (pin "11") (pinfunction "11_11") (pintype "passive"))
      (node (ref "X11") (pin "12") (pinfunction "12_12") (pintype "passive"))
      (node (ref "X11") (pin "9") (pinfunction "9_9") (pintype "passive"))
    )
    (net (code "31") (name "Net-(LED2-Pad2)") (class "Default")
      (node (ref "LED2") (pin "2") (pinfunction "2_2") (pintype "passive"))
      (node (ref "R82") (pin "2") (pinfunction "2_2") (pintype "passive"))
    )
    (net (code "32") (name "Net-(LED3-Pad2)") (class "Default")
      (node (ref "LED3") (pin "2") (pinfunction "2_2") (pintype "passive"))
      (node (ref "R87") (pin "2") (pinfunction "2_2") (pintype "passive"))
    )
    (net (code "33") (name "Net-(LED4-Pad2)") (class "Default")
      (node (ref "LED4") (pin "2") (pinfunction "2_2") (pintype "passive"))
      (node (ref "R93") (pin "2") (pinfunction "2_2") (pintype "passive"))
    )
    (net (code "34") (name "Net-(LED5-Pad2)") (class "Default")
      (node (ref "LED5") (pin "2") (pinfunction "2_2") (pintype "passive"))
      (node (ref "R97") (pin "2") (pinfunction "2_2") (pintype "passive"))
    )
    (net (code "35") (name "Net-(OPT1-Pad2)") (class "Default")
      (node (ref "OPT1") (pin "2") (pinfunction "2_2") (pintype "passive"))
      (node (ref "R80") (pin "1") (pinfunction "1_1") (pintype "passive"))
    )
    (net (code "36") (name "Net-(OPT1-Pad3)") (class "Default")
      (node (ref "OPT1") (pin "3") (pinfunction "3_3") (pintype "passive"))
      (node (ref "X12") (pin "2") (pinfunction "2_2") (pintype "passive"))
    )
    (net (code "37") (name "Net-(OPT1-Pad4)") (class "Default")
      (node (ref "OPT1") (pin "4") (pinfunction "4_4") (pintype "passive"))
      (node (ref "X12") (pin "1") (pinfunction "1_1") (pintype "passive"))
    )
    (net (code "38") (name "Net-(OPT2-Pad2)") (class "Default")
      (node (ref "OPT2") (pin "2") (pinfunction "2_2") (pintype "passive"))
      (node (ref "R86") (pin "1") (pinfunction "1_1") (pintype "passive"))
    )
    (net (code "39") (name "Net-(OPT2-Pad3)") (class "Default")
      (node (ref "OPT2") (pin "3") (pinfunction "3_3") (pintype "passive"))
      (node (ref "X13") (pin "2") (pinfunction "2_2") (pintype "passive"))
    )
    (net (code "40") (name "Net-(OPT2-Pad4)") (class "Default")
      (node (ref "OPT2") (pin "4") (pinfunction "4_4") (pintype "passive"))
      (node (ref "X13") (pin "1") (pinfunction "1_1") (pintype "passive"))
    )
    (net (code "41") (name "Net-(OPT3-Pad2)") (class "Default")
      (node (ref "OPT3") (pin "2") (pinfunction "2_2") (pintype "passive"))
      (node (ref "R91") (pin "1") (pinfunction "1_1") (pintype "passive"))
    )
    (net (code "42") (name "Net-(OPT3-Pad3)") (class "Default")
      (node (ref "OPT3") (pin "3") (pinfunction "3_3") (pintype "passive"))
      (node (ref "X14") (pin "2") (pinfunction "2_2") (pintype "passive"))
    )
    (net (code "43") (name "Net-(OPT3-Pad4)") (class "Default")
      (node (ref "OPT3") (pin "4") (pinfunction "4_4") (pintype "passive"))
      (node (ref "X14") (pin "1") (pinfunction "1_1") (pintype "passive"))
    )
    (net (code "44") (name "Net-(OPT4-Pad2)") (class "Default")
      (node (ref "OPT4") (pin "2") (pinfunction "2_2") (pintype "passive"))
      (node (ref "R96") (pin "1") (pinfunction "1_1") (pintype "passive"))
    )
    (net (code "45") (name "Net-(OPT4-Pad3)") (class "Default")
      (node (ref "OPT4") (pin "3") (pinfunction "3_3") (pintype "passive"))
      (node (ref "X15") (pin "2") (pinfunction "2_2") (pintype "passive"))
    )
    (net (code "46") (name "Net-(OPT4-Pad4)") (class "Default")
      (node (ref "OPT4") (pin "4") (pinfunction "4_4") (pintype "passive"))
      (node (ref "X15") (pin "1") (pinfunction "1_1") (pintype "passive"))
    )
    (net (code "47") (name "Net-(Q12-G)") (class "Default")
      (node (ref "C111") (pin "1") (pinfunction "1_1") (pintype "passive"))
      (node (ref "Q12") (pin "1") (pinfunction "G_1") (pintype "passive"))
      (node (ref "Q13") (pin "1") (pinfunction "G_1") (pintype "passive"))
      (node (ref "R75") (pin "2") (pinfunction "2_2") (pintype "passive"))
      (node (ref "VD17") (pin "1") (pinfunction "A_1") (pintype "passive"))
    )
    (net (code "48") (name "Net-(Q14-C)") (class "Default")
      (node (ref "OPT1") (pin "1") (pinfunction "1_1") (pintype "passive"))
      (node (ref "Q14") (pin "3") (pinfunction "C_3") (pintype "passive"))
      (node (ref "R82") (pin "1") (pinfunction "1_1") (pintype "passive"))
    )
    (net (code "49") (name "Net-(Q15-C)") (class "Default")
      (node (ref "OPT2") (pin "1") (pinfunction "1_1") (pintype "passive"))
      (node (ref "Q15") (pin "3") (pinfunction "C_3") (pintype "passive"))
      (node (ref "R87") (pin "1") (pinfunction "1_1") (pintype "passive"))
    )
    (net (code "50") (name "Net-(Q16-C)") (class "Default")
      (node (ref "OPT3") (pin "1") (pinfunction "1_1") (pintype "passive"))
      (node (ref "Q16") (pin "3") (pinfunction "C_3") (pintype "passive"))
      (node (ref "R93") (pin "1") (pinfunction "1_1") (pintype "passive"))
    )
    (net (code "51") (name "Net-(Q17-C)") (class "Default")
      (node (ref "OPT4") (pin "1") (pinfunction "1_1") (pintype "passive"))
      (node (ref "Q17") (pin "3") (pinfunction "C_3") (pintype "passive"))
      (node (ref "R97") (pin "1") (pinfunction "1_1") (pintype "passive"))
    )
    (net (code "52") (name "Net-(U23-OUT)") (class "Default")
      (node (ref "R71") (pin "1") (pinfunction "1_1") (pintype "passive"))
      (node (ref "U23") (pin "8") (pinfunction "OUT_8") (pintype "passive"))
    )
    (net (code "53") (name "Net-(U24-IN+)") (class "Default")
      (node (ref "C109") (pin "1") (pinfunction "1_1") (pintype "passive"))
      (node (ref "R72") (pin "2") (pinfunction "2_2") (pintype "passive"))
      (node (ref "R73") (pin "2") (pinfunction "2_2") (pintype "passive"))
      (node (ref "U24") (pin "3") (pinfunction "IN+_3") (pintype "passive"))
    )
    (net (code "54") (name "Net-(U24-IN-)") (class "Default")
      (node (ref "C107") (pin "2") (pinfunction "2_2") (pintype "passive"))
      (node (ref "R69") (pin "1") (pinfunction "1_1") (pintype "passive"))
      (node (ref "R70") (pin "2") (pinfunction "2_2") (pintype "passive"))
      (node (ref "U24") (pin "4") (pinfunction "IN-_4") (pintype "passive"))
    )
    (net (code "55") (name "Net-(U25-VDD2)") (class "Default")
      (node (ref "C117") (pin "2") (pinfunction "2_2") (pintype "passive"))
      (node (ref "U25") (pin "8") (pinfunction "VDD2_8") (pintype "passive"))
      (node (ref "U26") (pin "4") (pinfunction "+Vout_4") (pintype "passive"))
    )
    (net (code "56") (name "Net-(U25-VOC)") (class "Default")
      (node (ref "R75") (pin "1") (pinfunction "1_1") (pintype "passive"))
      (node (ref "U25") (pin "6") (pinfunction "VOC_6") (pintype "passive"))
      (node (ref "VD17") (pin "2") (pinfunction "C_2") (pintype "passive"))
    )
    (net (code "57") (name "Net-(U26-+Vin)") (class "Default")
      (node (ref "L8") (pin "2") (pinfunction "2_2") (pintype "passive"))
      (node (ref "U26") (pin "2") (pinfunction "+Vin_2") (pintype "passive"))
    )
    (net (code "58") (name "Net-(U27A-IN+)") (class "Default")
      (node (ref "C118") (pin "1") (pinfunction "1_1") (pintype "passive"))
      (node (ref "R78") (pin "2") (pinfunction "2_2") (pintype "passive"))
      (node (ref "R79") (pin "2") (pinfunction "2_2") (pintype "passive"))
      (node (ref "U27") (pin "3") (pinfunction "IN+_3") (pintype "passive"))
    )
    (net (code "59") (name "Net-(U27A-IN-)") (class "Default")
      (node (ref "C115") (pin "2") (pinfunction "2_2") (pintype "passive"))
      (node (ref "R76") (pin "1") (pinfunction "1_1") (pintype "passive"))
      (node (ref "R77") (pin "2") (pinfunction "2_2") (pintype "passive"))
      (node (ref "U27") (pin "2") (pinfunction "IN-_2") (pintype "passive"))
    )
    (net (code "60") (name "Net-(U27A-V+)") (class "Default")
      (node (ref "C112") (pin "1") (pinfunction "1_1") (pintype "passive"))
      (node (ref "C113") (pin "1") (pinfunction "1_1") (pintype "passive"))
      (node (ref "L7") (pin "2") (pinfunction "2_2") (pintype "passive"))
      (node (ref "U27") (pin "4") (pinfunction "V+_4") (pintype "power_in"))
    )
    (net (code "61") (name "Net-(U27B-IN+)") (class "Default")
      (node (ref "C121") (pin "1") (pinfunction "1_1") (pintype "passive"))
      (node (ref "R84") (pin "2") (pinfunction "2_2") (pintype "passive"))
      (node (ref "R85") (pin "2") (pinfunction "2_2") (pintype "passive"))
      (node (ref "U27") (pin "5") (pinfunction "IN+_5") (pintype "passive"))
    )
    (net (code "62") (name "Net-(U27B-IN-)") (class "Default")
      (node (ref "C120") (pin "2") (pinfunction "2_2") (pintype "passive"))
      (node (ref "R81") (pin "1") (pinfunction "1_1") (pintype "passive"))
      (node (ref "R83") (pin "2") (pinfunction "2_2") (pintype "passive"))
      (node (ref "U27") (pin "6") (pinfunction "IN-_6") (pintype "passive"))
    )
    (net (code "63") (name "Net-(U27C-IN+)") (class "Default")
      (node (ref "C123") (pin "1") (pinfunction "1_1") (pintype "passive"))
      (node (ref "R90") (pin "2") (pinfunction "2_2") (pintype "passive"))
      (node (ref "R92") (pin "2") (pinfunction "2_2") (pintype "passive"))
      (node (ref "U27") (pin "10") (pinfunction "IN+_10") (pintype "passive"))
    )
    (net (code "64") (name "Net-(U27C-IN-)") (class "Default")
      (node (ref "C122") (pin "2") (pinfunction "2_2") (pintype "passive"))
      (node (ref "R88") (pin "1") (pinfunction "1_1") (pintype "passive"))
      (node (ref "R89") (pin "2") (pinfunction "2_2") (pintype "passive"))
      (node (ref "U27") (pin "9") (pinfunction "IN-_9") (pintype "passive"))
    )
    (net (code "65") (name "Net-(U27D-IN+)") (class "Default")
      (node (ref "C125") (pin "1") (pinfunction "1_1") (pintype "passive"))
      (node (ref "R98") (pin "2") (pinfunction "2_2") (pintype "passive"))
      (node (ref "R99") (pin "2") (pinfunction "2_2") (pintype "passive"))
      (node (ref "U27") (pin "12") (pinfunction "IN+_12") (pintype "passive"))
    )
    (net (code "66") (name "Net-(U27D-IN-)") (class "Default")
      (node (ref "C124") (pin "2") (pinfunction "2_2") (pintype "passive"))
      (node (ref "R94") (pin "1") (pinfunction "1_1") (pintype "passive"))
      (node (ref "R95") (pin "2") (pinfunction "2_2") (pintype "passive"))
      (node (ref "U27") (pin "13") (pinfunction "IN-_13") (pintype "passive"))
    )
    (net (code "67") (name "PGND") (class "Default")
      (node (ref "R70") (pin "1") (pinfunction "1_1") (pintype "passive"))
      (node (ref "X10") (pin "1") (pinfunction "1_1") (pintype "passive"))
    )
    (net (code "68") (name "VREF_1.65V") (class "Default")
      (node (ref "C118") (pin "2") (pinfunction "2_2") (pintype "passive"))
      (node (ref "C119") (pin "2") (pinfunction "2_2") (pintype "passive"))
      (node (ref "C121") (pin "2") (pinfunction "2_2") (pintype "passive"))
      (node (ref "C123") (pin "2") (pinfunction "2_2") (pintype "passive"))
      (node (ref "C125") (pin "2") (pinfunction "2_2") (pintype "passive"))
      (node (ref "R79") (pin "1") (pinfunction "1_1") (pintype "passive"))
      (node (ref "R85") (pin "1") (pinfunction "1_1") (pintype "passive"))
      (node (ref "R92") (pin "1") (pinfunction "1_1") (pintype "passive"))
      (node (ref "R99") (pin "1") (pinfunction "1_1") (pintype "passive"))
    )
    (net (code "69") (name "unconnected-(U23-NC-Pad1)") (class "Default")
      (node (ref "U23") (pin "1") (pinfunction "NC_1") (pintype "passive"))
    )
    (net (code "70") (name "unconnected-(U25-VIB-Pad2)") (class "Default")
      (node (ref "U25") (pin "2") (pinfunction "VIB_2") (pintype "passive"))
    )
    (net (code "71") (name "unconnected-(U25-VOB-Pad7)") (class "Default")
      (node (ref "U25") (pin "7") (pinfunction "VOB_7") (pintype "passive"))
    )
  )
)
